# SENSOR_PHOTOTRANSISTOR.net
KiCad netlist of a schematic drawn in EAGLE
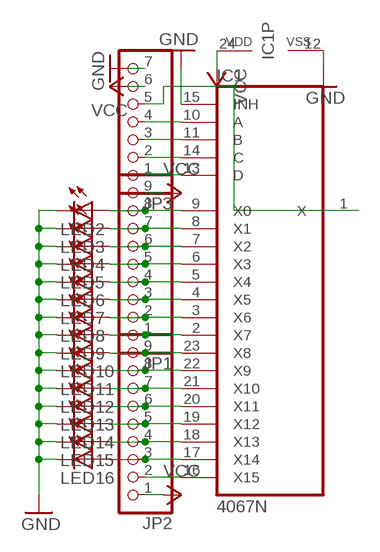
[diagram p0: schematic, sheet 1]

(export (version "E")
  (design (tool "Eeschema 10.0.6"))
  (components
    (comp (ref "IC1")
      (value "4067N")
      (footprint "eagle-import:DIL24-6")
      (libsource (lib "eagle-import") (part "4067N"))
    )
    (comp (ref "JP1")
      (value "PINHD-1X9")
      (footprint "eagle-import:1X09")
      (libsource (lib "eagle-import") (part "PINHD-1X9"))
    )
    (comp (ref "JP2")
      (value "PINHD-1X9")
      (footprint "eagle-import:1X09")
      (libsource (lib "eagle-import") (part "PINHD-1X9"))
    )
    (comp (ref "JP3")
      (value "PINHD-1X7")
      (footprint "eagle-import:1X07")
      (libsource (lib "eagle-import") (part "PINHD-1X7"))
    )
    (comp (ref "LED2")
      (value "LED5MM")
      (footprint "eagle-import:LED5MM")
      (libsource (lib "eagle-import") (part "LED5MM"))
    )
    (comp (ref "LED3")
      (value "LED5MM")
      (footprint "eagle-import:LED5MM")
      (libsource (lib "eagle-import") (part "LED5MM"))
    )
    (comp (ref "LED4")
      (value "LED5MM")
      (footprint "eagle-import:LED5MM")
      (libsource (lib "eagle-import") (part "LED5MM"))
    )
    (comp (ref "LED5")
      (value "LED5MM")
      (footprint "eagle-import:LED5MM")
      (libsource (lib "eagle-import") (part "LED5MM"))
    )
    (comp (ref "LED6")
      (value "LED5MM")
      (footprint "eagle-import:LED5MM")
      (libsource (lib "eagle-import") (part "LED5MM"))
    )
    (comp (ref "LED7")
      (value "LED5MM")
      (footprint "eagle-import:LED5MM")
      (libsource (lib "eagle-import") (part "LED5MM"))
    )
    (comp (ref "LED8")
      (value "LED5MM")
      (footprint "eagle-import:LED5MM")
      (libsource (lib "eagle-import") (part "LED5MM"))
    )
    (comp (ref "LED9")
      (value "LED5MM")
      (footprint "eagle-import:LED5MM")
      (libsource (lib "eagle-import") (part "LED5MM"))
    )
    (comp (ref "LED10")
      (value "LED5MM")
      (footprint "eagle-import:LED5MM")
      (libsource (lib "eagle-import") (part "LED5MM"))
    )
    (comp (ref "LED11")
      (value "LED5MM")
      (footprint "eagle-import:LED5MM")
      (libsource (lib "eagle-import") (part "LED5MM"))
    )
    (comp (ref "LED12")
      (value "LED5MM")
      (footprint "eagle-import:LED5MM")
      (libsource (lib "eagle-import") (part "LED5MM"))
    )
    (comp (ref "LED13")
      (value "LED5MM")
      (footprint "eagle-import:LED5MM")
      (libsource (lib "eagle-import") (part "LED5MM"))
    )
    (comp (ref "LED14")
      (value "LED5MM")
      (footprint "eagle-import:LED5MM")
      (libsource (lib "eagle-import") (part "LED5MM"))
    )
    (comp (ref "LED15")
      (value "LED5MM")
      (footprint "eagle-import:LED5MM")
      (libsource (lib "eagle-import") (part "LED5MM"))
    )
    (comp (ref "LED16")
      (value "LED5MM")
      (footprint "eagle-import:LED5MM")
      (libsource (lib "eagle-import") (part "LED5MM"))
    )
  )
  (nets
    (net (code "1") (name "GND") (class "Default")
      (node (ref "IC1") (pin "12") (pinfunction "VSS_12") (pintype "power_in"))
      (node (ref "IC1") (pin "15") (pinfunction "INH_15") (pintype "input"))
      (node (ref "JP3") (pin "7") (pinfunction "7_7") (pintype "passive"))
      (node (ref "LED10") (pin "K") (pinfunction "C_K") (pintype "passive"))
      (node (ref "LED11") (pin "K") (pinfunction "C_K") (pintype "passive"))
      (node (ref "LED12") (pin "K") (pinfunction "C_K") (pintype "passive"))
      (node (ref "LED13") (pin "K") (pinfunction "C_K") (pintype "passive"))
      (node (ref "LED14") (pin "K") (pinfunction "C_K") (pintype "passive"))
      (node (ref "LED15") (pin "K") (pinfunction "C_K") (pintype "passive"))
      (node (ref "LED16") (pin "K") (pinfunction "C_K") (pintype "passive"))
      (node (ref "LED2") (pin "K") (pinfunction "C_K") (pintype "passive"))
      (node (ref "LED3") (pin "K") (pinfunction "C_K") (pintype "passive"))
      (node (ref "LED4") (pin "K") (pinfunction "C_K") (pintype "passive"))
      (node (ref "LED5") (pin "K") (pinfunction "C_K") (pintype "passive"))
      (node (ref "LED6") (pin "K") (pinfunction "C_K") (pintype "passive"))
      (node (ref "LED7") (pin "K") (pinfunction "C_K") (pintype "passive"))
      (node (ref "LED8") (pin "K") (pinfunction "C_K") (pintype "passive"))
      (node (ref "LED9") (pin "K") (pinfunction "C_K") (pintype "passive"))
    )
    (net (code "2") (name "Net-(IC1A-A)") (class "Default")
      (node (ref "IC1") (pin "10") (pinfunction "A_10") (pintype "input"))
      (node (ref "JP3") (pin "4") (pinfunction "4_4") (pintype "passive"))
    )
    (net (code "3") (name "Net-(IC1A-B)") (class "Default")
      (node (ref "IC1") (pin "11") (pinfunction "B_11") (pintype "input"))
      (node (ref "JP3") (pin "3") (pinfunction "3_3") (pintype "passive"))
    )
    (net (code "4") (name "Net-(IC1A-C)") (class "Default")
      (node (ref "IC1") (pin "14") (pinfunction "C_14") (pintype "input"))
      (node (ref "JP3") (pin "2") (pinfunction "2_2") (pintype "passive"))
    )
    (net (code "5") (name "Net-(IC1A-D)") (class "Default")
      (node (ref "IC1") (pin "13") (pinfunction "D_13") (pintype "input"))
      (node (ref "JP3") (pin "1") (pinfunction "1_1") (pintype "passive"))
    )
    (net (code "6") (name "Net-(IC1A-X)") (class "Default")
      (node (ref "IC1") (pin "1") (pinfunction "X_1") (pintype "output"))
      (node (ref "JP3") (pin "5") (pinfunction "5_5") (pintype "passive"))
    )
    (net (code "7") (name "Net-(IC1A-X0)") (class "Default")
      (node (ref "IC1") (pin "9") (pinfunction "X0_9") (pintype "input"))
      (node (ref "JP1") (pin "8") (pinfunction "8_8") (pintype "passive"))
      (node (ref "LED2") (pin "A") (pinfunction "A_A") (pintype "passive"))
    )
    (net (code "8") (name "Net-(IC1A-X1)") (class "Default")
      (node (ref "IC1") (pin "8") (pinfunction "X1_8") (pintype "input"))
      (node (ref "JP1") (pin "7") (pinfunction "7_7") (pintype "passive"))
      (node (ref "LED3") (pin "A") (pinfunction "A_A") (pintype "passive"))
    )
    (net (code "9") (name "Net-(IC1A-X2)") (class "Default")
      (node (ref "IC1") (pin "7") (pinfunction "X2_7") (pintype "input"))
      (node (ref "JP1") (pin "6") (pinfunction "6_6") (pintype "passive"))
      (node (ref "LED4") (pin "A") (pinfunction "A_A") (pintype "passive"))
    )
    (net (code "10") (name "Net-(IC1A-X3)") (class "Default")
      (node (ref "IC1") (pin "6") (pinfunction "X3_6") (pintype "input"))
      (node (ref "JP1") (pin "5") (pinfunction "5_5") (pintype "passive"))
      (node (ref "LED5") (pin "A") (pinfunction "A_A") (pintype "passive"))
    )
    (net (code "11") (name "Net-(IC1A-X4)") (class "Default")
      (node (ref "IC1") (pin "5") (pinfunction "X4_5") (pintype "input"))
      (node (ref "JP1") (pin "4") (pinfunction "4_4") (pintype "passive"))
      (node (ref "LED6") (pin "A") (pinfunction "A_A") (pintype "passive"))
    )
    (net (code "12") (name "Net-(IC1A-X5)") (class "Default")
      (node (ref "IC1") (pin "4") (pinfunction "X5_4") (pintype "input"))
      (node (ref "JP1") (pin "3") (pinfunction "3_3") (pintype "passive"))
      (node (ref "LED7") (pin "A") (pinfunction "A_A") (pintype "passive"))
    )
    (net (code "13") (name "Net-(IC1A-X6)") (class "Default")
      (node (ref "IC1") (pin "3") (pinfunction "X6_3") (pintype "input"))
      (node (ref "JP1") (pin "2") (pinfunction "2_2") (pintype "passive"))
      (node (ref "LED8") (pin "A") (pinfunction "A_A") (pintype "passive"))
    )
    (net (code "14") (name "Net-(IC1A-X7)") (class "Default")
      (node (ref "IC1") (pin "2") (pinfunction "X7_2") (pintype "input"))
      (node (ref "JP1") (pin "1") (pinfunction "1_1") (pintype "passive"))
      (node (ref "LED9") (pin "A") (pinfunction "A_A") (pintype "passive"))
    )
    (net (code "15") (name "Net-(IC1A-X8)") (class "Default")
      (node (ref "IC1") (pin "23") (pinfunction "X8_23") (pintype "input"))
      (node (ref "JP2") (pin "9") (pinfunction "9_9") (pintype "passive"))
      (node (ref "LED10") (pin "A") (pinfunction "A_A") (pintype "passive"))
    )
    (net (code "16") (name "Net-(IC1A-X9)") (class "Default")
      (node (ref "IC1") (pin "22") (pinfunction "X9_22") (pintype "input"))
      (node (ref "JP2") (pin "8") (pinfunction "8_8") (pintype "passive"))
      (node (ref "LED11") (pin "A") (pinfunction "A_A") (pintype "passive"))
    )
    (net (code "17") (name "Net-(IC1A-X10)") (class "Default")
      (node (ref "IC1") (pin "21") (pinfunction "X10_21") (pintype "input"))
      (node (ref "JP2") (pin "7") (pinfunction "7_7") (pintype "passive"))
      (node (ref "LED12") (pin "A") (pinfunction "A_A") (pintype "passive"))
    )
    (net (code "18") (name "Net-(IC1A-X11)") (class "Default")
      (node (ref "IC1") (pin "20") (pinfunction "X11_20") (pintype "input"))
      (node (ref "JP2") (pin "6") (pinfunction "6_6") (pintype "passive"))
      (node (ref "LED13") (pin "A") (pinfunction "A_A") (pintype "passive"))
    )
    (net (code "19") (name "Net-(IC1A-X12)") (class "Default")
      (node (ref "IC1") (pin "19") (pinfunction "X12_19") (pintype "input"))
      (node (ref "JP2") (pin "5") (pinfunction "5_5") (pintype "passive"))
      (node (ref "LED14") (pin "A") (pinfunction "A_A") (pintype "passive"))
    )
    (net (code "20") (name "Net-(IC1A-X13)") (class "Default")
      (node (ref "IC1") (pin "18") (pinfunction "X13_18") (pintype "input"))
      (node (ref "JP2") (pin "4") (pinfunction "4_4") (pintype "passive"))
      (node (ref "LED15") (pin "A") (pinfunction "A_A") (pintype "passive"))
    )
    (net (code "21") (name "Net-(IC1A-X14)") (class "Default")
      (node (ref "IC1") (pin "17") (pinfunction "X14_17") (pintype "input"))
      (node (ref "JP2") (pin "3") (pinfunction "3_3") (pintype "passive"))
      (node (ref "LED16") (pin "A") (pinfunction "A_A") (pintype "passive"))
    )
    (net (code "22") (name "Net-(IC1A-X15)") (class "Default")
      (node (ref "IC1") (pin "16") (pinfunction "X15_16") (pintype "input"))
      (node (ref "JP2") (pin "2") (pinfunction "2_2") (pintype "passive"))
    )
    (net (code "23") (name "VCC") (class "Default")
      (node (ref "IC1") (pin "24") (pinfunction "VDD_24") (pintype "power_in"))
      (node (ref "JP1") (pin "9") (pinfunction "9_9") (pintype "passive"))
      (node (ref "JP2") (pin "1") (pinfunction "1_1") (pintype "passive"))
      (node (ref "JP3") (pin "6") (pinfunction "6_6") (pintype "passive"))
    )
  )
)
